# Schematic_FPC.net
KiCad netlist of a schematic drawn in Altium Designer
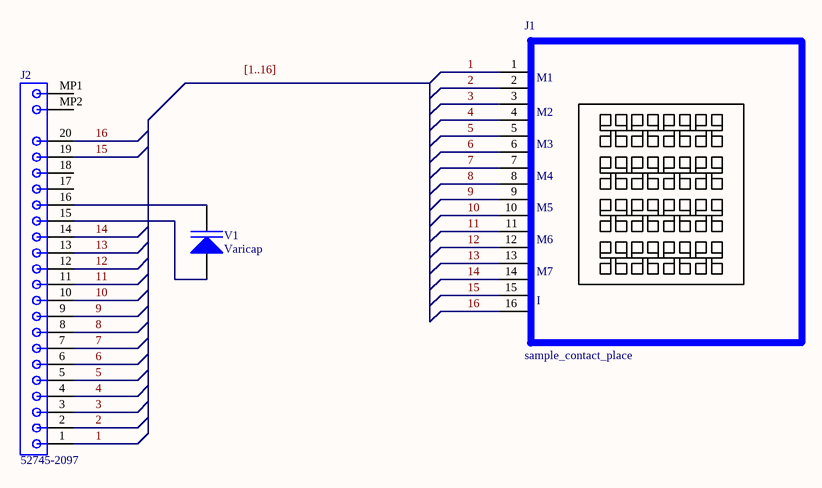
[diagram p0: Schematic_FPC.SchDoc]

(export (version "E")
  (design (tool "Eeschema 10.0.6"))
  (components
    (comp (ref "J1")
      (value "sample_contact_place")
      (footprint "sample")
      (libsource (lib "sample_holder_library") (part "sample_contact_place"))
    )
    (comp (ref "J2")
      (value "52745-2097")
      (footprint "MOLX-52745-2097")
      (fields (field (name "MANUFACTURER") "Molex"))
      (libsource (lib "sample_holder_library") (part "52745-2097"))
    )
    (comp (ref "V1")
      (value "Varicap")
      (footprint "DIOC160X80X70L20N")
      (libsource (lib "sample_holder_library") (part "Varicap"))
    )
  )
  (nets
    (net (code "1") (name "/1") (class "Default")
      (node (ref "J1") (pin "1") (pinfunction "1_1") (pintype "passive"))
      (node (ref "J2") (pin "1") (pinfunction "1_1") (pintype "passive"))
    )
    (net (code "2") (name "/2") (class "Default")
      (node (ref "J1") (pin "2") (pinfunction "2_2") (pintype "passive"))
      (node (ref "J2") (pin "2") (pinfunction "2_2") (pintype "passive"))
    )
    (net (code "3") (name "/3") (class "Default")
      (node (ref "J1") (pin "3") (pinfunction "3_3") (pintype "passive"))
      (node (ref "J2") (pin "3") (pinfunction "3_3") (pintype "passive"))
    )
    (net (code "4") (name "/4") (class "Default")
      (node (ref "J1") (pin "4") (pinfunction "4_4") (pintype "passive"))
      (node (ref "J2") (pin "4") (pinfunction "4_4") (pintype "passive"))
    )
    (net (code "5") (name "/5") (class "Default")
      (node (ref "J1") (pin "5") (pinfunction "5_5") (pintype "passive"))
      (node (ref "J2") (pin "5") (pinfunction "5_5") (pintype "passive"))
    )
    (net (code "6") (name "/6") (class "Default")
      (node (ref "J1") (pin "6") (pinfunction "6_6") (pintype "passive"))
      (node (ref "J2") (pin "6") (pinfunction "6_6") (pintype "passive"))
    )
    (net (code "7") (name "/7") (class "Default")
      (node (ref "J1") (pin "7") (pinfunction "7_7") (pintype "passive"))
      (node (ref "J2") (pin "7") (pinfunction "7_7") (pintype "passive"))
    )
    (net (code "8") (name "/8") (class "Default")
      (node (ref "J1") (pin "8") (pinfunction "8_8") (pintype "passive"))
      (node (ref "J2") (pin "8") (pinfunction "8_8") (pintype "passive"))
    )
    (net (code "9") (name "/9") (class "Default")
      (node (ref "J1") (pin "9") (pinfunction "9_9") (pintype "passive"))
      (node (ref "J2") (pin "9") (pinfunction "9_9") (pintype "passive"))
    )
    (net (code "10") (name "/10") (class "Default")
      (node (ref "J1") (pin "10") (pinfunction "10_10") (pintype "passive"))
      (node (ref "J2") (pin "10") (pinfunction "10_10") (pintype "passive"))
    )
    (net (code "11") (name "/11") (class "Default")
      (node (ref "J1") (pin "11") (pinfunction "11_11") (pintype "passive"))
      (node (ref "J2") (pin "11") (pinfunction "11_11") (pintype "passive"))
    )
    (net (code "12") (name "/12") (class "Default")
      (node (ref "J1") (pin "12") (pinfunction "12_12") (pintype "passive"))
      (node (ref "J2") (pin "12") (pinfunction "12_12") (pintype "passive"))
    )
    (net (code "13") (name "/13") (class "Default")
      (node (ref "J1") (pin "13") (pinfunction "13_13") (pintype "passive"))
      (node (ref "J2") (pin "13") (pinfunction "13_13") (pintype "passive"))
    )
    (net (code "14") (name "/14") (class "Default")
      (node (ref "J1") (pin "14") (pinfunction "14_14") (pintype "passive"))
      (node (ref "J2") (pin "14") (pinfunction "14_14") (pintype "passive"))
    )
    (net (code "15") (name "/15") (class "Default")
      (node (ref "J1") (pin "15") (pinfunction "15_15") (pintype "passive"))
      (node (ref "J2") (pin "19") (pinfunction "19_19") (pintype "passive"))
    )
    (net (code "16") (name "/16") (class "Default")
      (node (ref "J1") (pin "16") (pinfunction "16_16") (pintype "passive"))
      (node (ref "J2") (pin "20") (pinfunction "20_20") (pintype "passive"))
    )
    (net (code "18") (name "Net-(J2-Pad15)") (class "Default")
      (node (ref "J2") (pin "15") (pinfunction "15_15") (pintype "passive"))
      (node (ref "V1") (pin "A") (pinfunction "A_A") (pintype "passive"))
    )
    (net (code "19") (name "Net-(J2-Pad16)") (class "Default")
      (node (ref "J2") (pin "16") (pinfunction "16_16") (pintype "passive"))
      (node (ref "V1") (pin "C") (pinfunction "C_C") (pintype "passive"))
    )
    (net (code "20") (name "unconnected-(J2-Pad17)") (class "Default")
      (node (ref "J2") (pin "17") (pinfunction "17_17") (pintype "passive"))
    )
    (net (code "21") (name "unconnected-(J2-Pad18)") (class "Default")
      (node (ref "J2") (pin "18") (pinfunction "18_18") (pintype "passive"))
    )
    (net (code "22") (name "unconnected-(J2-PadMP1)") (class "Default")
      (node (ref "J2") (pin "MP1") (pinfunction "MP1_MP1") (pintype "passive"))
    )
    (net (code "23") (name "unconnected-(J2-PadMP2)") (class "Default")
      (node (ref "J2") (pin "MP2") (pinfunction "MP2_MP2") (pintype "passive"))
    )
  )
)
